# Ethernet.net
KiCad netlist of a schematic drawn in Altium Designer
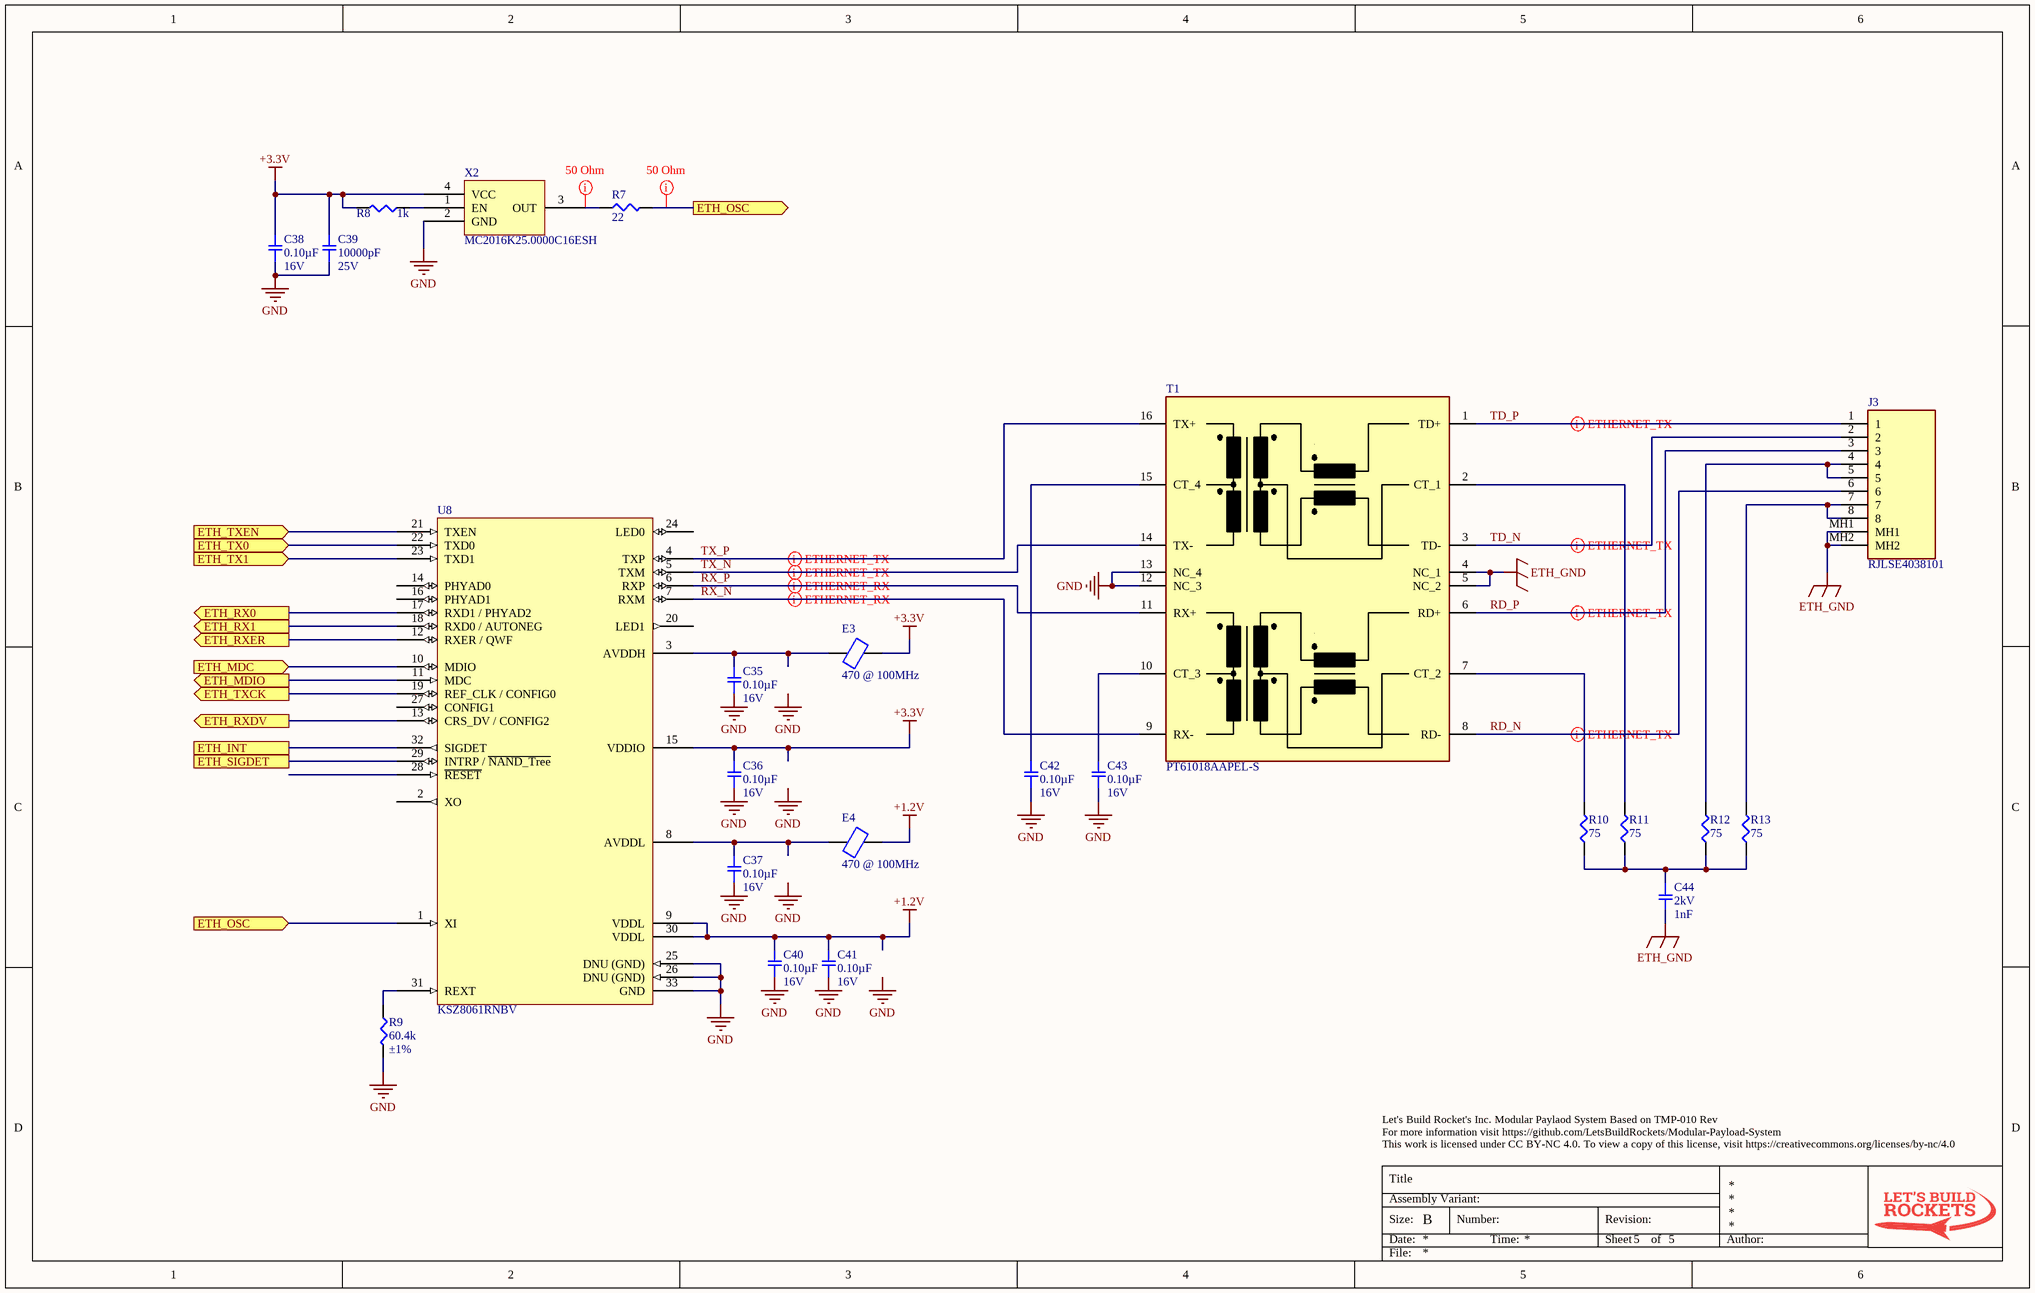
[diagram p0: Ethernet.SchDoc]

(export (version "E")
  (design (tool "Eeschema 10.0.6"))
  (components
    (comp (ref "C35")
      (value "0.10µF")
      (footprint "SMD-0402C")
      (description "CAP CER 0.1UF 16V X7R 0402")
      (fields
        (field (name "DIGI-KEY PART NUMBER") "490-4759-1-ND")
        (field (name "PART NUMBER") "GCM155R71C104KA55D")
        (field (name "VOLTAGE") "16V")
      )
      (libsource (lib "capacitor_murata_0402") (part "GCM155R71C104KA55D"))
    )
    (comp (ref "C36")
      (value "0.10µF")
      (footprint "SMD-0402C")
      (description "CAP CER 0.1UF 16V X7R 0402")
      (fields
        (field (name "DIGI-KEY PART NUMBER") "490-4759-1-ND")
        (field (name "PART NUMBER") "GCM155R71C104KA55D")
        (field (name "VOLTAGE") "16V")
      )
      (libsource (lib "capacitor_murata_0402") (part "GCM155R71C104KA55D"))
    )
    (comp (ref "C37")
      (value "0.10µF")
      (footprint "SMD-0402C")
      (description "CAP CER 0.1UF 16V X7R 0402")
      (fields
        (field (name "DIGI-KEY PART NUMBER") "490-4759-1-ND")
        (field (name "PART NUMBER") "GCM155R71C104KA55D")
        (field (name "VOLTAGE") "16V")
      )
      (libsource (lib "capacitor_murata_0402") (part "GCM155R71C104KA55D"))
    )
    (comp (ref "C38")
      (value "0.10µF")
      (footprint "SMD-0402C")
      (description "CAP CER 0.1UF 16V X7R 0402")
      (fields
        (field (name "DIGI-KEY PART NUMBER") "490-4759-1-ND")
        (field (name "PART NUMBER") "GCM155R71C104KA55D")
        (field (name "VOLTAGE") "16V")
      )
      (libsource (lib "capacitor_murata_0402") (part "GCM155R71C104KA55D"))
    )
    (comp (ref "C39")
      (value "10000pF")
      (footprint "SMD-0402C")
      (description "CAP CER 10000PF 25V X7R 0402")
      (fields
        (field (name "DIGI-KEY PART NUMBER") "490-6043-1-ND")
        (field (name "PART NUMBER") "GCM155R71E103KA37D")
        (field (name "VOLTAGE") "25V")
      )
      (libsource (lib "capacitor_murata_0402") (part "GCM155R71E103KA37D"))
    )
    (comp (ref "C40")
      (value "0.10µF")
      (footprint "SMD-0402C")
      (description "CAP CER 0.1UF 16V X7R 0402")
      (fields
        (field (name "DIGI-KEY PART NUMBER") "490-4759-1-ND")
        (field (name "PART NUMBER") "GCM155R71C104KA55D")
        (field (name "VOLTAGE") "16V")
      )
      (libsource (lib "capacitor_murata_0402") (part "GCM155R71C104KA55D"))
    )
    (comp (ref "C41")
      (value "0.10µF")
      (footprint "SMD-0402C")
      (description "CAP CER 0.1UF 16V X7R 0402")
      (fields
        (field (name "DIGI-KEY PART NUMBER") "490-4759-1-ND")
        (field (name "PART NUMBER") "GCM155R71C104KA55D")
        (field (name "VOLTAGE") "16V")
      )
      (libsource (lib "capacitor_murata_0402") (part "GCM155R71C104KA55D"))
    )
    (comp (ref "C42")
      (value "0.10µF")
      (footprint "SMD-0402C")
      (description "CAP CER 0.1UF 16V X7R 0402")
      (fields
        (field (name "DIGI-KEY PART NUMBER") "490-4759-1-ND")
        (field (name "PART NUMBER") "GCM155R71C104KA55D")
        (field (name "VOLTAGE") "16V")
      )
      (libsource (lib "capacitor_murata_0402") (part "GCM155R71C104KA55D"))
    )
    (comp (ref "C43")
      (value "0.10µF")
      (footprint "SMD-0402C")
      (description "CAP CER 0.1UF 16V X7R 0402")
      (fields
        (field (name "DIGI-KEY PART NUMBER") "490-4759-1-ND")
        (field (name "PART NUMBER") "GCM155R71C104KA55D")
        (field (name "VOLTAGE") "16V")
      )
      (libsource (lib "capacitor_murata_0402") (part "GCM155R71C104KA55D"))
    )
    (comp (ref "C44")
      (value "1nF")
      (footprint "SMD-1206C")
      (fields (field (name "VOLTAGE") "2kV") (field (name "Comment") "C1206C102KGRACAUTO"))
      (libsource (lib "KEMET") (part "C1206C102KGRACAUTO"))
    )
    (comp (ref "E3")
      (value "470 @ 100MHz")
      (fields (field (name "Comment") "MPZ1608S471ATD25"))
      (libsource (lib "ModularPayload") (part "MPZ1608S471ATD25"))
    )
    (comp (ref "E4")
      (value "470 @ 100MHz")
      (fields (field (name "Comment") "MPZ1608S471ATD25"))
      (libsource (lib "ModularPayload") (part "MPZ1608S471ATD25"))
    )
    (comp (ref "J3")
      (value "RJLSE4038101")
      (footprint "RJLSE4038101")
      (description "Connector")
      (fields (field (name "MOUSER2 PART NUMBER") "523-RJLSE4038101"))
      (libsource (lib "ModularPayload") (part "RJLSE4038101"))
    )
    (comp (ref "R7")
      (value "22")
      (footprint "SMD-0402-RES")
      (description "RES SMD 22 OHM 1% 1/10W 0402")
      (fields
        (field (name "PART NUMBER") "ERJ-2RKF22R0X")
        (field (name "DIGI-KEY PART NUMBER") "P22.0LCT-ND")
      )
      (libsource (lib "Panasonic_ERJ_0402") (part "ERJ-2RKF22R0X"))
    )
    (comp (ref "R8")
      (value "1k")
      (footprint "SMD-0402-RES")
      (description "RES SMD 1K OHM 5% 1/10W 0402")
      (fields (field (name "PART NUMBER") "ERJ-2GEJ102X") (field (name "DIGI-KEY PART NUMBER") "P1.0KJCT-ND"))
      (libsource (lib "Panasonic_ERJ_0402") (part "ERJ-2GEJ102X"))
    )
    (comp (ref "R9")
      (value "60.4k")
      (footprint "SMD-0402-RES")
      (description "RES SMD 60.4K OHM 1% 1/10W 0402")
      (fields
        (field (name "PART NUMBER") "ERJ-2RKF6042X")
        (field (name "DIGI-KEY PART NUMBER") "P60.4KLCT-ND")
        (field (name "TOLERANCE") "±1%")
      )
      (libsource (lib "Panasonic_ERJ_0402") (part "ERJ-2RKF6042X"))
    )
    (comp (ref "R10")
      (value "75")
      (footprint "SMD-0402-RES")
      (description "RES SMD 75 OHM 5% 1/10W 0402")
      (fields (field (name "PART NUMBER") "ERJ-2GEJ750X") (field (name "DIGI-KEY PART NUMBER") "P75JCT-ND"))
      (libsource (lib "Panasonic_ERJ_0402") (part "ERJ-2GEJ750X"))
    )
    (comp (ref "R11")
      (value "75")
      (footprint "SMD-0402-RES")
      (description "RES SMD 75 OHM 5% 1/10W 0402")
      (fields (field (name "PART NUMBER") "ERJ-2GEJ750X") (field (name "DIGI-KEY PART NUMBER") "P75JCT-ND"))
      (libsource (lib "Panasonic_ERJ_0402") (part "ERJ-2GEJ750X"))
    )
    (comp (ref "R12")
      (value "75")
      (footprint "SMD-0402-RES")
      (description "RES SMD 75 OHM 5% 1/10W 0402")
      (fields (field (name "PART NUMBER") "ERJ-2GEJ750X") (field (name "DIGI-KEY PART NUMBER") "P75JCT-ND"))
      (libsource (lib "Panasonic_ERJ_0402") (part "ERJ-2GEJ750X"))
    )
    (comp (ref "R13")
      (value "75")
      (footprint "SMD-0402-RES")
      (description "RES SMD 75 OHM 5% 1/10W 0402")
      (fields (field (name "PART NUMBER") "ERJ-2GEJ750X") (field (name "DIGI-KEY PART NUMBER") "P75JCT-ND"))
      (libsource (lib "Panasonic_ERJ_0402") (part "ERJ-2GEJ750X"))
    )
    (comp (ref "T1")
      (value "PT61018AAPEL-S")
      (footprint "SOIC127P930X590-16N")
      (description "Transformer")
      (libsource (lib "ModularPayload") (part "PT61018AAPEL-S"))
    )
    (comp (ref "U8") (value "KSZ8061RNBV") (libsource (lib "ModularPayload") (part "KSZ8061RNBV")))
    (comp (ref "X2")
      (value "MC2016K25.0000C16ESH")
      (footprint "MC2016")
      (libsource (lib "ModularPayload") (part "MC2016K25.0000C16ESH"))
    )
  )
  (nets
    (net (code "1") (name "+1.2V") (class "Default")
      (node (ref "C40") (pin "2") (pinfunction "2_2") (pintype "passive"))
      (node (ref "C41") (pin "2") (pinfunction "2_2") (pintype "passive"))
      (node (ref "E4") (pin "2") (pinfunction "2_2") (pintype "passive"))
      (node (ref "U8") (pin "30") (pinfunction "VDDL_30") (pintype "power_in"))
      (node (ref "U8") (pin "9") (pinfunction "VDDL_9") (pintype "power_in"))
    )
    (net (code "2") (name "+3.3V") (class "Default")
      (node (ref "C36") (pin "2") (pinfunction "2_2") (pintype "passive"))
      (node (ref "C38") (pin "2") (pinfunction "2_2") (pintype "passive"))
      (node (ref "C39") (pin "2") (pinfunction "2_2") (pintype "passive"))
      (node (ref "E3") (pin "2") (pinfunction "2_2") (pintype "passive"))
      (node (ref "R8") (pin "2") (pinfunction "2_2") (pintype "passive"))
      (node (ref "U8") (pin "15") (pinfunction "VDDIO_15") (pintype "power_in"))
      (node (ref "X2") (pin "4") (pinfunction "VCC_4") (pintype "passive"))
    )
    (net (code "3") (name "/ETH_INT") (class "Default")
      (node (ref "U8") (pin "32") (pinfunction "SIGDET_32") (pintype "output"))
    )
    (net (code "4") (name "/ETH_MDC") (class "Default")
      (node (ref "U8") (pin "10") (pinfunction "MDIO_10") (pintype "bidirectional"))
    )
    (net (code "5") (name "/ETH_MDIO") (class "Default")
      (node (ref "U8") (pin "11") (pinfunction "MDC_11") (pintype "input"))
    )
    (net (code "6") (name "/ETH_OSC") (class "Default")
      (node (ref "R7") (pin "2") (pinfunction "2_2") (pintype "passive"))
      (node (ref "U8") (pin "1") (pinfunction "XI_1") (pintype "input"))
    )
    (net (code "7") (name "/ETH_RX0") (class "Default")
      (node (ref "U8") (pin "17") (pinfunction "RXD1_/_PHYAD2_17") (pintype "bidirectional"))
    )
    (net (code "8") (name "/ETH_RX1") (class "Default")
      (node (ref "U8") (pin "18") (pinfunction "RXD0_/_AUTONEG_18") (pintype "bidirectional"))
    )
    (net (code "9") (name "/ETH_RXDV") (class "Default")
      (node (ref "U8") (pin "13") (pinfunction "CRS_DV_/_CONFIG2_13") (pintype "bidirectional"))
    )
    (net (code "10") (name "/ETH_RXER") (class "Default")
      (node (ref "U8") (pin "12") (pinfunction "RXER_/_QWF_12") (pintype "bidirectional"))
    )
    (net (code "11") (name "/ETH_SIGDET") (class "Default")
      (node (ref "U8") (pin "29") (pinfunction "INTRP_/_~{NAND_Tree}_29") (pintype "bidirectional"))
    )
    (net (code "12") (name "/ETH_TX0") (class "Default")
      (node (ref "U8") (pin "22") (pinfunction "TXD0_22") (pintype "input"))
    )
    (net (code "13") (name "/ETH_TX1") (class "Default")
      (node (ref "U8") (pin "23") (pinfunction "TXD1_23") (pintype "input"))
    )
    (net (code "14") (name "/ETH_TXCK") (class "Default")
      (node (ref "U8") (pin "19") (pinfunction "REF_CLK_/_CONFIG0_19") (pintype "bidirectional"))
    )
    (net (code "15") (name "/ETH_TXEN") (class "Default")
      (node (ref "U8") (pin "21") (pinfunction "TXEN_21") (pintype "input"))
    )
    (net (code "16") (name "/RD_N") (class "Default")
      (node (ref "J3") (pin "6") (pinfunction "6_6") (pintype "passive"))
      (node (ref "T1") (pin "8") (pinfunction "RD-_8") (pintype "passive"))
    )
    (net (code "17") (name "/RD_P") (class "Default")
      (node (ref "J3") (pin "3") (pinfunction "3_3") (pintype "passive"))
      (node (ref "T1") (pin "6") (pinfunction "RD+_6") (pintype "passive"))
    )
    (net (code "18") (name "/RX_N") (class "Default")
      (node (ref "T1") (pin "9") (pinfunction "RX-_9") (pintype "passive"))
      (node (ref "U8") (pin "7") (pinfunction "RXM_7") (pintype "bidirectional"))
    )
    (net (code "19") (name "/RX_P") (class "Default")
      (node (ref "T1") (pin "11") (pinfunction "RX+_11") (pintype "passive"))
      (node (ref "U8") (pin "6") (pinfunction "RXP_6") (pintype "bidirectional"))
    )
    (net (code "20") (name "/TD_N") (class "Default")
      (node (ref "J3") (pin "2") (pinfunction "2_2") (pintype "passive"))
      (node (ref "T1") (pin "3") (pinfunction "TD-_3") (pintype "passive"))
    )
    (net (code "21") (name "/TD_P") (class "Default")
      (node (ref "J3") (pin "1") (pinfunction "1_1") (pintype "passive"))
      (node (ref "T1") (pin "1") (pinfunction "TD+_1") (pintype "passive"))
    )
    (net (code "22") (name "/TX_N") (class "Default")
      (node (ref "T1") (pin "14") (pinfunction "TX-_14") (pintype "passive"))
      (node (ref "U8") (pin "5") (pinfunction "TXM_5") (pintype "bidirectional"))
    )
    (net (code "23") (name "/TX_P") (class "Default")
      (node (ref "T1") (pin "16") (pinfunction "TX+_16") (pintype "passive"))
      (node (ref "U8") (pin "4") (pinfunction "TXP_4") (pintype "bidirectional"))
    )
    (net (code "24") (name "ETH_GND") (class "Default")
      (node (ref "C44") (pin "2") (pinfunction "2_2") (pintype "passive"))
      (node (ref "J3") (pin "MH1") (pinfunction "MH1_MH1") (pintype "passive"))
      (node (ref "J3") (pin "MH2") (pinfunction "MH2_MH2") (pintype "passive"))
      (node (ref "T1") (pin "4") (pinfunction "NC_1_4") (pintype "passive"))
      (node (ref "T1") (pin "5") (pinfunction "NC_2_5") (pintype "passive"))
    )
    (net (code "25") (name "GND") (class "Default")
      (node (ref "C35") (pin "1") (pinfunction "1_1") (pintype "passive"))
      (node (ref "C36") (pin "1") (pinfunction "1_1") (pintype "passive"))
      (node (ref "C37") (pin "1") (pinfunction "1_1") (pintype "passive"))
      (node (ref "C38") (pin "1") (pinfunction "1_1") (pintype "passive"))
      (node (ref "C39") (pin "1") (pinfunction "1_1") (pintype "passive"))
      (node (ref "C40") (pin "1") (pinfunction "1_1") (pintype "passive"))
      (node (ref "C41") (pin "1") (pinfunction "1_1") (pintype "passive"))
      (node (ref "C42") (pin "1") (pinfunction "1_1") (pintype "passive"))
      (node (ref "C43") (pin "1") (pinfunction "1_1") (pintype "passive"))
      (node (ref "R9") (pin "2") (pinfunction "2_2") (pintype "passive"))
      (node (ref "T1") (pin "12") (pinfunction "NC_3_12") (pintype "passive"))
      (node (ref "T1") (pin "13") (pinfunction "NC_4_13") (pintype "passive"))
      (node (ref "U8") (pin "25") (pinfunction "DNU_(GND)_25") (pintype "input"))
      (node (ref "U8") (pin "26") (pinfunction "DNU_(GND)_26") (pintype "input"))
      (node (ref "U8") (pin "33") (pinfunction "GND_33") (pintype "power_in"))
      (node (ref "X2") (pin "2") (pinfunction "GND_2") (pintype "passive"))
    )
    (net (code "26") (name "Net-(C44-Pad1)") (class "Default")
      (node (ref "C44") (pin "1") (pinfunction "1_1") (pintype "passive"))
      (node (ref "R10") (pin "1") (pinfunction "1_1") (pintype "passive"))
      (node (ref "R11") (pin "1") (pinfunction "1_1") (pintype "passive"))
      (node (ref "R12") (pin "1") (pinfunction "1_1") (pintype "passive"))
      (node (ref "R13") (pin "1") (pinfunction "1_1") (pintype "passive"))
    )
    (net (code "27") (name "Net-(J3-Pad4)") (class "Default")
      (node (ref "J3") (pin "4") (pinfunction "4_4") (pintype "passive"))
      (node (ref "J3") (pin "5") (pinfunction "5_5") (pintype "passive"))
      (node (ref "R12") (pin "2") (pinfunction "2_2") (pintype "passive"))
    )
    (net (code "28") (name "Net-(J3-Pad7)") (class "Default")
      (node (ref "J3") (pin "7") (pinfunction "7_7") (pintype "passive"))
      (node (ref "J3") (pin "8") (pinfunction "8_8") (pintype "passive"))
      (node (ref "R13") (pin "2") (pinfunction "2_2") (pintype "passive"))
    )
    (net (code "29") (name "Net-(T1-CT_1)") (class "Default")
      (node (ref "R11") (pin "2") (pinfunction "2_2") (pintype "passive"))
      (node (ref "T1") (pin "2") (pinfunction "CT_1_2") (pintype "passive"))
    )
    (net (code "30") (name "Net-(T1-CT_2)") (class "Default")
      (node (ref "R10") (pin "2") (pinfunction "2_2") (pintype "passive"))
      (node (ref "T1") (pin "7") (pinfunction "CT_2_7") (pintype "passive"))
    )
    (net (code "31") (name "Net-(T1-CT_3)") (class "Default")
      (node (ref "C43") (pin "2") (pinfunction "2_2") (pintype "passive"))
      (node (ref "T1") (pin "10") (pinfunction "CT_3_10") (pintype "passive"))
    )
    (net (code "32") (name "Net-(T1-CT_4)") (class "Default")
      (node (ref "C42") (pin "2") (pinfunction "2_2") (pintype "passive"))
      (node (ref "T1") (pin "15") (pinfunction "CT_4_15") (pintype "passive"))
    )
    (net (code "33") (name "Net-(U8-AVDDH)") (class "Default")
      (node (ref "C35") (pin "2") (pinfunction "2_2") (pintype "passive"))
      (node (ref "E3") (pin "1") (pinfunction "1_1") (pintype "passive"))
      (node (ref "U8") (pin "3") (pinfunction "AVDDH_3") (pintype "power_in"))
    )
    (net (code "34") (name "Net-(U8-AVDDL)") (class "Default")
      (node (ref "C37") (pin "2") (pinfunction "2_2") (pintype "passive"))
      (node (ref "E4") (pin "1") (pinfunction "1_1") (pintype "passive"))
      (node (ref "U8") (pin "8") (pinfunction "AVDDL_8") (pintype "power_in"))
    )
    (net (code "35") (name "Net-(U8-REXT)") (class "Default")
      (node (ref "R9") (pin "1") (pinfunction "1_1") (pintype "passive"))
      (node (ref "U8") (pin "31") (pinfunction "REXT_31") (pintype "input"))
    )
    (net (code "36") (name "Net-(X2-EN)") (class "Default")
      (node (ref "R8") (pin "1") (pinfunction "1_1") (pintype "passive"))
      (node (ref "X2") (pin "1") (pinfunction "EN_1") (pintype "passive"))
    )
    (net (code "37") (name "Net-(X2-OUT)") (class "Default")
      (node (ref "R7") (pin "1") (pinfunction "1_1") (pintype "passive"))
      (node (ref "X2") (pin "3") (pinfunction "OUT_3") (pintype "passive"))
    )
    (net (code "38") (name "unconnected-(U8-CONFIG1-Pad27)") (class "Default")
      (node (ref "U8") (pin "27") (pinfunction "CONFIG1_27") (pintype "bidirectional"))
    )
    (net (code "39") (name "unconnected-(U8-LED0-Pad24)") (class "Default")
      (node (ref "U8") (pin "24") (pinfunction "LED0_24") (pintype "bidirectional"))
    )
    (net (code "40") (name "unconnected-(U8-LED1-Pad20)") (class "Default")
      (node (ref "U8") (pin "20") (pinfunction "LED1_20") (pintype "output"))
    )
    (net (code "41") (name "unconnected-(U8-PHYAD0-Pad14)") (class "Default")
      (node (ref "U8") (pin "14") (pinfunction "PHYAD0_14") (pintype "bidirectional"))
    )
    (net (code "42") (name "unconnected-(U8-PHYAD1-Pad16)") (class "Default")
      (node (ref "U8") (pin "16") (pinfunction "PHYAD1_16") (pintype "bidirectional"))
    )
    (net (code "43") (name "unconnected-(U8-XO-Pad2)") (class "Default")
      (node (ref "U8") (pin "2") (pinfunction "XO_2") (pintype "output"))
    )
    (net (code "44") (name "unconnected-(U8-~{RESET}-Pad28)") (class "Default")
      (node (ref "U8") (pin "28") (pinfunction "~{RESET}_28") (pintype "input"))
    )
  )
)
